# A4950_driver.net
KiCad netlist of a schematic drawn in Altium Designer
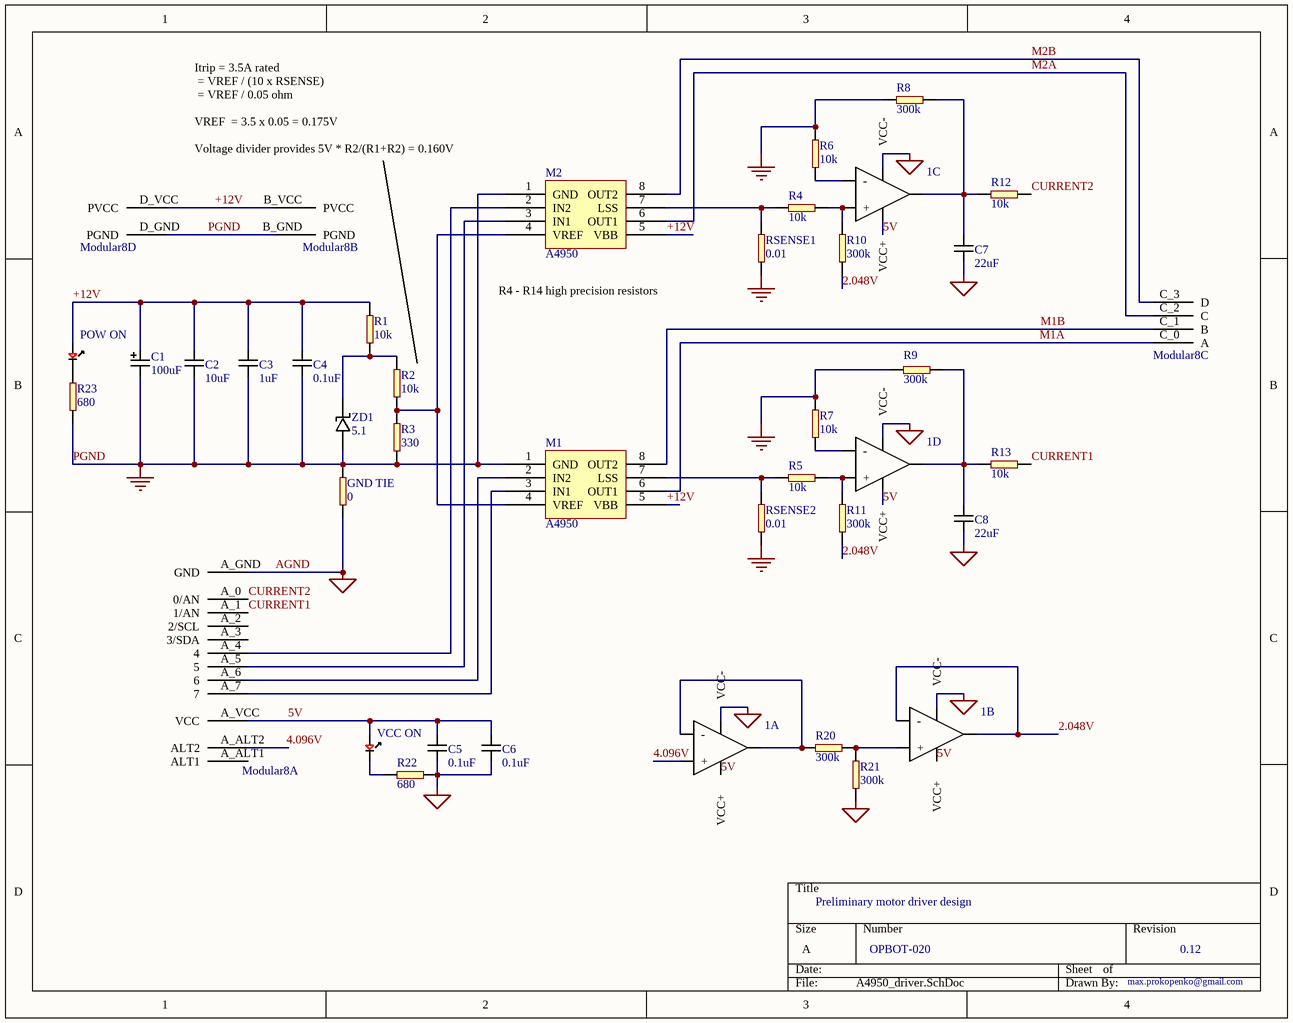
[diagram p0: A4950_driver.SchDoc]

(export (version "E")
  (design (tool "Eeschema 10.0.6"))
  (components
    (comp (ref "1") (value "LM324DT") (footprint "SO14") (libsource (lib "OpBots") (part "LM324DT")))
    (comp (ref "C1")
      (value "C 100uF 25V")
      (footprint "RADIAL CAP 6.5mm")
      (fields (field (name "C") "100uF"))
      (libsource (lib "RLC") (part "C 100uF 25V"))
    )
    (comp (ref "C2")
      (value "C 10uF 25V")
      (footprint "0603")
      (fields (field (name "C") "10uF"))
      (libsource (lib "RLC") (part "C 10uF 25V"))
    )
    (comp (ref "C3")
      (value "C 1uF 25V")
      (footprint "0603")
      (fields (field (name "C") "1uF"))
      (libsource (lib "RLC") (part "C 1uF 25V"))
    )
    (comp (ref "C4")
      (value "C 0.1uF 25V")
      (footprint "0603")
      (fields (field (name "C") "0.1uF"))
      (libsource (lib "RLC") (part "C 0.1uF 25V"))
    )
    (comp (ref "C5")
      (value "C 0.1uF 25V")
      (footprint "0603")
      (fields (field (name "C") "0.1uF"))
      (libsource (lib "RLC") (part "C 0.1uF 25V"))
    )
    (comp (ref "C6")
      (value "C 0.1uF 25V")
      (footprint "0603")
      (fields (field (name "C") "0.1uF"))
      (libsource (lib "RLC") (part "C 0.1uF 25V"))
    )
    (comp (ref "C7")
      (value "C 22uF 6.3V")
      (footprint "0603")
      (fields (field (name "C") "22uF"))
      (libsource (lib "RLC") (part "C 22uF 6.3V"))
    )
    (comp (ref "C8")
      (value "C 22uF 6.3V")
      (footprint "0603")
      (fields (field (name "C") "22uF"))
      (libsource (lib "RLC") (part "C 22uF 6.3V"))
    )
    (comp (ref "GND TIE")
      (value "R 0")
      (footprint "0603")
      (fields (field (name "R") "0"))
      (libsource (lib "RLC") (part "R 0"))
    )
    (comp (ref "M1")
      (value "A4950")
      (footprint "SOICN8 thermal pad")
      (libsource (lib "OpBots") (part "A4950"))
    )
    (comp (ref "M2")
      (value "A4950")
      (footprint "SOICN8 thermal pad")
      (libsource (lib "OpBots") (part "A4950"))
    )
    (comp (ref "Modular8")
      (value "modular8_power")
      (footprint "modular8 metric power")
      (libsource (lib "OpBots") (part "modular8_power"))
    )
    (comp (ref "POW ON") (value "LEDG") (footprint "0805 - LED") (libsource (lib "OpBots") (part "LEDG")))
    (comp (ref "R1")
      (value "R 10k")
      (footprint "0603")
      (fields (field (name "R") "10k"))
      (libsource (lib "") (part "R 10k_1"))
    )
    (comp (ref "R2")
      (value "R 10k")
      (footprint "0603")
      (fields (field (name "R") "10k"))
      (libsource (lib "") (part "R 10k_1"))
    )
    (comp (ref "R3")
      (value "R 330")
      (footprint "0603")
      (fields (field (name "R") "330"))
      (libsource (lib "RLC") (part "R 330"))
    )
    (comp (ref "R4")
      (value "R 10k 1%")
      (footprint "0603")
      (fields (field (name "R") "10k"))
      (libsource (lib "RLC") (part "R 10k 1%"))
    )
    (comp (ref "R5")
      (value "R 10k 1%")
      (footprint "0603")
      (fields (field (name "R") "10k"))
      (libsource (lib "RLC") (part "R 10k 1%"))
    )
    (comp (ref "R6")
      (value "R 10k 1%")
      (footprint "0603")
      (fields (field (name "R") "10k"))
      (libsource (lib "") (part "R 10k 1%_1"))
    )
    (comp (ref "R7")
      (value "R 10k 1%")
      (footprint "0603")
      (fields (field (name "R") "10k"))
      (libsource (lib "") (part "R 10k 1%_1"))
    )
    (comp (ref "R8")
      (value "R 300k 1%")
      (footprint "0603")
      (fields (field (name "R") "300k"))
      (libsource (lib "") (part "R 300k 1%_1"))
    )
    (comp (ref "R9")
      (value "R 300k 1%")
      (footprint "0603")
      (fields (field (name "R") "300k"))
      (libsource (lib "") (part "R 300k 1%_1"))
    )
    (comp (ref "R10")
      (value "R 300k 1%")
      (footprint "0603")
      (fields (field (name "R") "300k"))
      (libsource (lib "") (part "R 300k 1%_2"))
    )
    (comp (ref "R11")
      (value "R 300k 1%")
      (footprint "0603")
      (fields (field (name "R") "300k"))
      (libsource (lib "") (part "R 300k 1%_2"))
    )
    (comp (ref "R12")
      (value "R 10k")
      (footprint "0603")
      (fields (field (name "R") "10k"))
      (libsource (lib "RLC") (part "R 10k"))
    )
    (comp (ref "R13")
      (value "R 10k")
      (footprint "0603")
      (fields (field (name "R") "10k"))
      (libsource (lib "RLC") (part "R 10k"))
    )
    (comp (ref "R20")
      (value "R 300k 1%")
      (footprint "0603")
      (fields (field (name "R") "300k"))
      (libsource (lib "RLC") (part "R 300k 1%"))
    )
    (comp (ref "R21")
      (value "R 300k 1%")
      (footprint "0603")
      (fields (field (name "R") "300k"))
      (libsource (lib "") (part "R 300k 1%_2"))
    )
    (comp (ref "R22")
      (value "R 680")
      (footprint "0603")
      (fields (field (name "R") "680"))
      (libsource (lib "") (part "R 680_1"))
    )
    (comp (ref "R23")
      (value "R 680")
      (footprint "0603")
      (fields (field (name "R") "680"))
      (libsource (lib "RLC") (part "R 680"))
    )
    (comp (ref "RSENSE1")
      (value "R 0.01 0.5%")
      (footprint "1206 SPLIT")
      (fields (field (name "R") "0.01"))
      (libsource (lib "RLC") (part "R 0.01 0.5%"))
    )
    (comp (ref "RSENSE2")
      (value "R 0.01 0.5%")
      (footprint "1206 SPLIT")
      (fields (field (name "R") "0.01"))
      (libsource (lib "RLC") (part "R 0.01 0.5%"))
    )
    (comp (ref "VCC ON") (value "LEDG") (footprint "0805 - LED") (libsource (lib "OpBots") (part "LEDG")))
    (comp (ref "ZD1")
      (value "Zener 5.1V")
      (footprint "SOD-323F")
      (fields (field (name "VOLTAGE") "5.1"))
      (libsource (lib "OpBots") (part "Zener 5.1V"))
    )
  )
  (nets
    (net (code "1") (name "/+12V") (class "Default")
      (node (ref "C1") (pin "1") (pintype "passive"))
      (node (ref "C2") (pin "1") (pintype "passive"))
      (node (ref "C3") (pin "1") (pintype "passive"))
      (node (ref "C4") (pin "1") (pintype "passive"))
      (node (ref "M1") (pin "5") (pinfunction "VBB_5") (pintype "passive"))
      (node (ref "M2") (pin "5") (pinfunction "VBB_5") (pintype "passive"))
      (node (ref "Modular8") (pin "B_VCC") (pinfunction "PVCC_B_VCC") (pintype "passive"))
      (node (ref "Modular8") (pin "D_VCC") (pinfunction "PVCC_D_VCC") (pintype "passive"))
      (node (ref "POW ON") (pin "2") (pinfunction "A_2") (pintype "passive"))
      (node (ref "R1") (pin "1") (pintype "passive"))
    )
    (net (code "2") (name "/2.048V") (class "Default")
      (node (ref "1") (pin "6") (pinfunction "-_6") (pintype "passive"))
      (node (ref "1") (pin "7") (pinfunction "OUT_7") (pintype "passive"))
      (node (ref "R10") (pin "2") (pintype "passive"))
      (node (ref "R11") (pin "2") (pintype "passive"))
    )
    (net (code "3") (name "/4.096V") (class "Default")
      (node (ref "1") (pin "3") (pinfunction "+_3") (pintype "passive"))
      (node (ref "Modular8") (pin "A_ALT2") (pinfunction "ALT2_A_ALT2") (pintype "passive"))
    )
    (net (code "4") (name "/5V") (class "Default")
      (node (ref "1") (pin "4") (pinfunction "VCC+_4") (pintype "passive"))
      (node (ref "C5") (pin "1") (pintype "passive"))
      (node (ref "C6") (pin "1") (pintype "passive"))
      (node (ref "Modular8") (pin "A_VCC") (pinfunction "VCC_A_VCC") (pintype "passive"))
      (node (ref "VCC ON") (pin "2") (pinfunction "A_2") (pintype "passive"))
    )
    (net (code "5") (name "/CURRENT1") (class "Default")
      (node (ref "Modular8") (pin "A_1") (pinfunction "1/AN_A_1") (pintype "passive"))
      (node (ref "R13") (pin "2") (pintype "passive"))
    )
    (net (code "6") (name "/CURRENT2") (class "Default")
      (node (ref "Modular8") (pin "A_0") (pinfunction "0/AN_A_0") (pintype "passive"))
      (node (ref "R12") (pin "2") (pintype "passive"))
    )
    (net (code "7") (name "/M1A") (class "Default")
      (node (ref "M1") (pin "6") (pinfunction "OUT1_6") (pintype "passive"))
      (node (ref "Modular8") (pin "C_0") (pinfunction "A_C_0") (pintype "passive"))
    )
    (net (code "8") (name "/M1B") (class "Default")
      (node (ref "M1") (pin "8") (pinfunction "OUT2_8") (pintype "passive"))
      (node (ref "Modular8") (pin "C_1") (pinfunction "B_C_1") (pintype "passive"))
    )
    (net (code "9") (name "/M2A") (class "Default")
      (node (ref "M2") (pin "6") (pinfunction "OUT1_6") (pintype "passive"))
      (node (ref "Modular8") (pin "C_2") (pinfunction "C_C_2") (pintype "passive"))
    )
    (net (code "10") (name "/M2B") (class "Default")
      (node (ref "M2") (pin "8") (pinfunction "OUT2_8") (pintype "passive"))
      (node (ref "Modular8") (pin "C_3") (pinfunction "D_C_3") (pintype "passive"))
    )
    (net (code "11") (name "AGND") (class "Default")
      (node (ref "1") (pin "11") (pinfunction "VCC-_11") (pintype "passive"))
      (node (ref "C5") (pin "2") (pintype "passive"))
      (node (ref "C6") (pin "2") (pintype "passive"))
      (node (ref "C7") (pin "2") (pintype "passive"))
      (node (ref "C8") (pin "2") (pintype "passive"))
      (node (ref "GND TIE") (pin "2") (pintype "passive"))
      (node (ref "Modular8") (pin "A_GND") (pinfunction "GND_A_GND") (pintype "passive"))
      (node (ref "R21") (pin "2") (pintype "passive"))
      (node (ref "R22") (pin "2") (pintype "passive"))
    )
    (net (code "12") (name "Net-(1A--)") (class "Default")
      (node (ref "1") (pin "1") (pinfunction "OUT_1") (pintype "passive"))
      (node (ref "1") (pin "2") (pinfunction "-_2") (pintype "passive"))
      (node (ref "R20") (pin "2") (pintype "passive"))
    )
    (net (code "13") (name "Net-(1B-+)") (class "Default")
      (node (ref "1") (pin "5") (pinfunction "+_5") (pintype "passive"))
      (node (ref "R20") (pin "1") (pintype "passive"))
      (node (ref "R21") (pin "1") (pintype "passive"))
    )
    (net (code "14") (name "Net-(1C-+)") (class "Default")
      (node (ref "1") (pin "10") (pinfunction "+_10") (pintype "passive"))
      (node (ref "R10") (pin "1") (pintype "passive"))
      (node (ref "R4") (pin "2") (pintype "passive"))
    )
    (net (code "15") (name "Net-(1C--)") (class "Default")
      (node (ref "1") (pin "9") (pinfunction "-_9") (pintype "passive"))
      (node (ref "R6") (pin "1") (pintype "passive"))
    )
    (net (code "16") (name "Net-(1C-OUT)") (class "Default")
      (node (ref "1") (pin "8") (pinfunction "OUT_8") (pintype "passive"))
      (node (ref "C7") (pin "1") (pintype "passive"))
      (node (ref "R12") (pin "1") (pintype "passive"))
      (node (ref "R8") (pin "2") (pintype "passive"))
    )
    (net (code "17") (name "Net-(1D-+)") (class "Default")
      (node (ref "1") (pin "12") (pinfunction "+_12") (pintype "passive"))
      (node (ref "R11") (pin "1") (pintype "passive"))
      (node (ref "R5") (pin "2") (pintype "passive"))
    )
    (net (code "18") (name "Net-(1D--)") (class "Default")
      (node (ref "1") (pin "13") (pinfunction "-_13") (pintype "passive"))
      (node (ref "R7") (pin "1") (pintype "passive"))
    )
    (net (code "19") (name "Net-(1D-OUT)") (class "Default")
      (node (ref "1") (pin "14") (pinfunction "OUT_14") (pintype "passive"))
      (node (ref "C8") (pin "1") (pintype "passive"))
      (node (ref "R13") (pin "1") (pintype "passive"))
      (node (ref "R9") (pin "2") (pintype "passive"))
    )
    (net (code "20") (name "Net-(M1-IN1)") (class "Default")
      (node (ref "M1") (pin "3") (pinfunction "IN1_3") (pintype "passive"))
      (node (ref "Modular8") (pin "A_7") (pinfunction "7_A_7") (pintype "passive"))
    )
    (net (code "21") (name "Net-(M1-IN2)") (class "Default")
      (node (ref "M1") (pin "2") (pinfunction "IN2_2") (pintype "passive"))
      (node (ref "Modular8") (pin "A_6") (pinfunction "6_A_6") (pintype "passive"))
    )
    (net (code "22") (name "Net-(M1-LSS)") (class "Default")
      (node (ref "M1") (pin "7") (pinfunction "LSS_7") (pintype "passive"))
      (node (ref "R5") (pin "1") (pintype "passive"))
      (node (ref "RSENSE2") (pin "1") (pintype "passive"))
    )
    (net (code "23") (name "Net-(M1-VREF)") (class "Default")
      (node (ref "M1") (pin "4") (pinfunction "VREF_4") (pintype "passive"))
      (node (ref "M2") (pin "4") (pinfunction "VREF_4") (pintype "passive"))
      (node (ref "R2") (pin "2") (pintype "passive"))
      (node (ref "R3") (pin "1") (pintype "passive"))
    )
    (net (code "24") (name "Net-(M2-IN1)") (class "Default")
      (node (ref "M2") (pin "3") (pinfunction "IN1_3") (pintype "passive"))
      (node (ref "Modular8") (pin "A_5") (pinfunction "5_A_5") (pintype "passive"))
    )
    (net (code "25") (name "Net-(M2-IN2)") (class "Default")
      (node (ref "M2") (pin "2") (pinfunction "IN2_2") (pintype "passive"))
      (node (ref "Modular8") (pin "A_4") (pinfunction "4_A_4") (pintype "passive"))
    )
    (net (code "26") (name "Net-(M2-LSS)") (class "Default")
      (node (ref "M2") (pin "7") (pinfunction "LSS_7") (pintype "passive"))
      (node (ref "R4") (pin "1") (pintype "passive"))
      (node (ref "RSENSE1") (pin "1") (pintype "passive"))
    )
    (net (code "27") (name "Net-(POW ON-K)") (class "Default")
      (node (ref "POW ON") (pin "1") (pinfunction "K_1") (pintype "passive"))
      (node (ref "R23") (pin "1") (pintype "passive"))
    )
    (net (code "28") (name "Net-(R1-Pad2)") (class "Default")
      (node (ref "R1") (pin "2") (pintype "passive"))
      (node (ref "R2") (pin "1") (pintype "passive"))
      (node (ref "ZD1") (pin "2") (pintype "passive"))
    )
    (net (code "29") (name "Net-(VCC ON-K)") (class "Default")
      (node (ref "R22") (pin "1") (pintype "passive"))
      (node (ref "VCC ON") (pin "1") (pinfunction "K_1") (pintype "passive"))
    )
    (net (code "30") (name "PGND") (class "Default")
      (node (ref "C1") (pin "2") (pintype "passive"))
      (node (ref "C2") (pin "2") (pintype "passive"))
      (node (ref "C3") (pin "2") (pintype "passive"))
      (node (ref "C4") (pin "2") (pintype "passive"))
      (node (ref "GND TIE") (pin "1") (pintype "passive"))
      (node (ref "M1") (pin "1") (pinfunction "GND_1") (pintype "passive"))
      (node (ref "M2") (pin "1") (pinfunction "GND_1") (pintype "passive"))
      (node (ref "Modular8") (pin "B_GND") (pinfunction "PGND_B_GND") (pintype "passive"))
      (node (ref "Modular8") (pin "D_GND") (pinfunction "PGND_D_GND") (pintype "passive"))
      (node (ref "R23") (pin "2") (pintype "passive"))
      (node (ref "R3") (pin "2") (pintype "passive"))
      (node (ref "R6") (pin "2") (pintype "passive"))
      (node (ref "R7") (pin "2") (pintype "passive"))
      (node (ref "R8") (pin "1") (pintype "passive"))
      (node (ref "R9") (pin "1") (pintype "passive"))
      (node (ref "RSENSE1") (pin "2") (pintype "passive"))
      (node (ref "RSENSE2") (pin "2") (pintype "passive"))
      (node (ref "ZD1") (pin "1") (pintype "passive"))
    )
    (net (code "31") (name "unconnected-(Modular8A-2{slash}SCL-PadA_2)") (class "Default")
      (node (ref "Modular8") (pin "A_2") (pinfunction "2/SCL_A_2") (pintype "passive"))
    )
    (net (code "32") (name "unconnected-(Modular8A-3{slash}SDA-PadA_3)") (class "Default")
      (node (ref "Modular8") (pin "A_3") (pinfunction "3/SDA_A_3") (pintype "passive"))
    )
    (net (code "33") (name "unconnected-(Modular8A-ALT1-PadA_ALT1)") (class "Default")
      (node (ref "Modular8") (pin "A_ALT1") (pinfunction "ALT1_A_ALT1") (pintype "passive"))
    )
  )
)
